# Crystal_Test_V1.net
KiCad netlist of a schematic drawn in Altium Designer
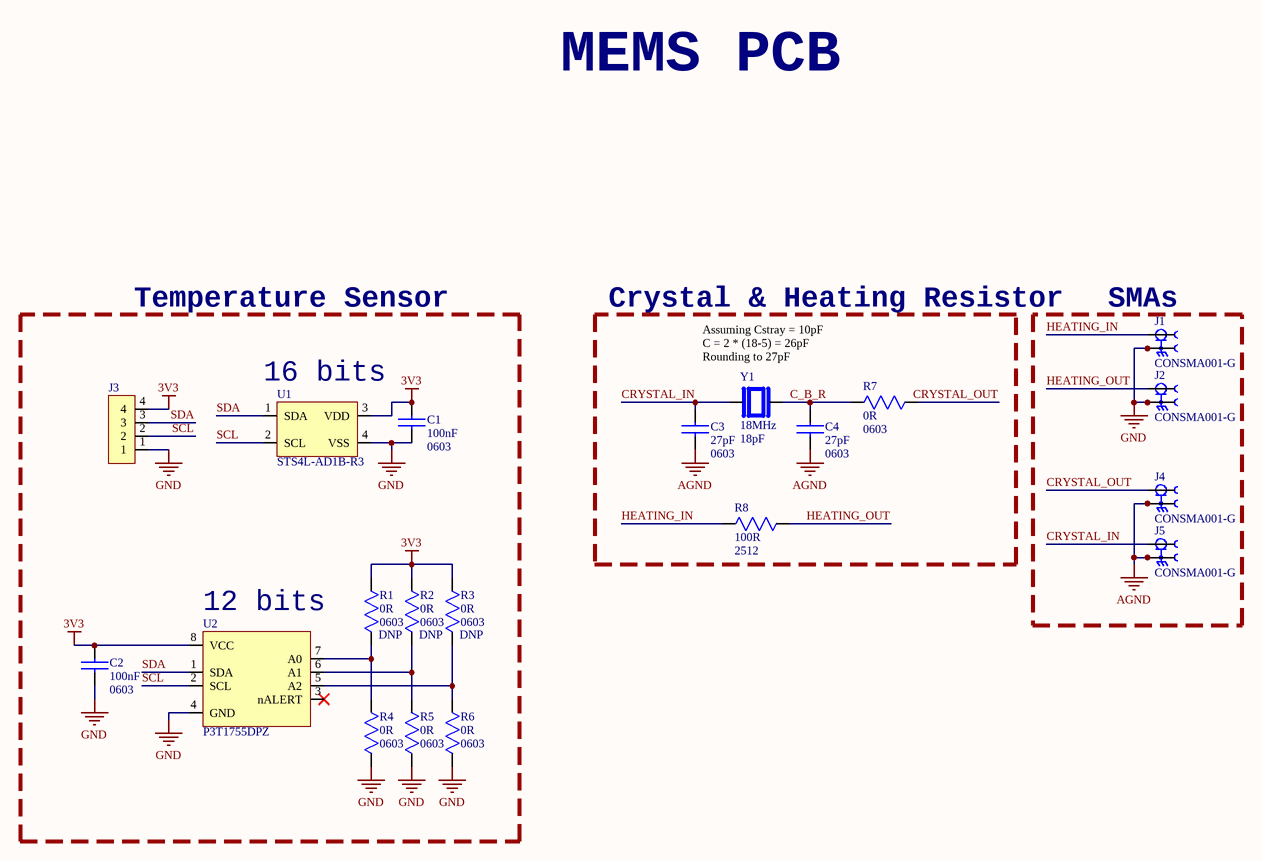
[diagram p0: Crystal_Test_V1.SchDoc]

(export (version "E")
  (design (tool "Eeschema 10.0.6"))
  (components
    (comp (ref "C1")
      (value "100nF")
      (footprint "C0603")
      (description "CAP CER 100NF 100V X8L 0603")
      (fields
        (field (name "MANUFACTURER") "Samsung")
        (field (name "MANUFACTURER PART NUMBER") "CL10E104KC8VPNC")
        (field (name "CASE") "0603")
      )
      (libsource (lib "MEMS_LIB") (part "CL10E104KC8VPNC"))
    )
    (comp (ref "C2")
      (value "100nF")
      (footprint "C0603")
      (description "CAP CER 100NF 100V X8L 0603")
      (fields
        (field (name "MANUFACTURER") "Samsung")
        (field (name "MANUFACTURER PART NUMBER") "CL10E104KC8VPNC")
        (field (name "CASE") "0603")
      )
      (libsource (lib "MEMS_LIB") (part "CL10E104KC8VPNC"))
    )
    (comp (ref "C3")
      (value "27pF")
      (footprint "C0603")
      (description "CAP CER 27PF 50V C0G/NP0 0603")
      (fields (field (name "PACKAGING") "0603") (field (name "Comment") "C0603C270J5GACTU"))
      (libsource (lib "MEMS_LIB") (part "C0603C270J5GACTU"))
    )
    (comp (ref "C4")
      (value "27pF")
      (footprint "C0603")
      (description "CAP CER 27PF 50V C0G/NP0 0603")
      (fields (field (name "PACKAGING") "0603") (field (name "Comment") "C0603C270J5GACTU"))
      (libsource (lib "MEMS_LIB") (part "C0603C270J5GACTU"))
    )
    (comp (ref "J1")
      (value "CONSMA001-G")
      (footprint "CONSMA001-G")
      (description "CONN SMA RCPT STR 50 OHM PCB")
      (libsource (lib "MEMS_LIB") (part "CONSMA001-G"))
    )
    (comp (ref "J2")
      (value "CONSMA001-G")
      (footprint "CONSMA001-G")
      (description "CONN SMA RCPT STR 50 OHM PCB")
      (libsource (lib "MEMS_LIB") (part "CONSMA001-G"))
    )
    (comp (ref "J3")
      (value "61300411121")
      (footprint "WURTH_61300411121")
      (description "CONN HEADER VERT 4POS 2.54MM")
      (fields (field (name "MF") "WÃ¼rth Elektronik"))
      (libsource (lib "MEMS_LIB") (part "61300411121"))
    )
    (comp (ref "J4")
      (value "CONSMA001-G")
      (footprint "CONSMA001-G")
      (description "CONN SMA RCPT STR 50 OHM PCB")
      (libsource (lib "MEMS_LIB") (part "CONSMA001-G"))
    )
    (comp (ref "J5")
      (value "CONSMA001-G")
      (footprint "CONSMA001-G")
      (description "CONN SMA RCPT STR 50 OHM PCB")
      (libsource (lib "MEMS_LIB") (part "CONSMA001-G"))
    )
    (comp (ref "R1")
      (value "0R")
      (footprint "R0603")
      (description "RES 0 OHM JUMPER 1/10W 0603")
      (fields
        (field (name "MF") "Stackpole Electronics")
        (field (name "MP") "RMCF0603ZT0R00")
        (field (name "PACKAGE") "0603")
      )
      (libsource (lib "MEMS_LIB") (part "RMCF0603ZT0R00"))
    )
    (comp (ref "R2")
      (value "0R")
      (footprint "R0603")
      (description "RES 0 OHM JUMPER 1/10W 0603")
      (fields
        (field (name "MF") "Stackpole Electronics")
        (field (name "MP") "RMCF0603ZT0R00")
        (field (name "PACKAGE") "0603")
      )
      (libsource (lib "MEMS_LIB") (part "RMCF0603ZT0R00"))
    )
    (comp (ref "R3")
      (value "0R")
      (footprint "R0603")
      (description "RES 0 OHM JUMPER 1/10W 0603")
      (fields
        (field (name "MF") "Stackpole Electronics")
        (field (name "MP") "RMCF0603ZT0R00")
        (field (name "PACKAGE") "0603")
      )
      (libsource (lib "MEMS_LIB") (part "RMCF0603ZT0R00"))
    )
    (comp (ref "R4")
      (value "0R")
      (footprint "R0603")
      (description "RES 0 OHM JUMPER 1/10W 0603")
      (fields
        (field (name "MF") "Stackpole Electronics")
        (field (name "MP") "RMCF0603ZT0R00")
        (field (name "PACKAGE") "0603")
      )
      (libsource (lib "MEMS_LIB") (part "RMCF0603ZT0R00"))
    )
    (comp (ref "R5")
      (value "0R")
      (footprint "R0603")
      (description "RES 0 OHM JUMPER 1/10W 0603")
      (fields
        (field (name "MF") "Stackpole Electronics")
        (field (name "MP") "RMCF0603ZT0R00")
        (field (name "PACKAGE") "0603")
      )
      (libsource (lib "MEMS_LIB") (part "RMCF0603ZT0R00"))
    )
    (comp (ref "R6")
      (value "0R")
      (footprint "R0603")
      (description "RES 0 OHM JUMPER 1/10W 0603")
      (fields
        (field (name "MF") "Stackpole Electronics")
        (field (name "MP") "RMCF0603ZT0R00")
        (field (name "PACKAGE") "0603")
      )
      (libsource (lib "MEMS_LIB") (part "RMCF0603ZT0R00"))
    )
    (comp (ref "R7")
      (value "0R")
      (footprint "R0603")
      (description "RES 0 OHM JUMPER 1/10W 0603")
      (fields
        (field (name "MF") "Stackpole Electronics")
        (field (name "MP") "RMCF0603ZT0R00")
        (field (name "PACKAGE") "0603")
      )
      (libsource (lib "MEMS_LIB") (part "RMCF0603ZT0R00"))
    )
    (comp (ref "R8")
      (value "100R")
      (footprint "R2512")
      (description "RES SMD 100 OHM 1% 1W 2512")
      (fields (field (name "PACKAGING") "2512") (field (name "Comment") "CRCW2512100RFKEG"))
      (libsource (lib "MEMS_LIB") (part "CRCW2512100RFKEG"))
    )
    (comp (ref "U1")
      (value "STS4L-AD1B-R3")
      (footprint "STS4L-AD1B-R3")
      (description "IC - TEMPERATURE SENSOR 4-DFN")
      (libsource (lib "MEMS_LIB") (part "STS4L-AD1B-R3"))
    )
    (comp (ref "U2")
      (value "P3T1755DPZ")
      (footprint "TSSOP8_P3T1755DPZ_NXP")
      (description "SENSOR DGTL -40C ~ 125C 8-TSSOP")
      (libsource (lib "MEMS_LIB") (part "P3T1755DPZ"))
    )
    (comp (ref "Y1")
      (value "18MHz")
      (footprint "XTAL_ABLS-18.000MHZ-B4-T")
      (description "CRYSTAL 18.0000MHZ 18PF SMD")
      (fields
        (field (name "MF") "Abracon")
        (field (name "MP") "ABLS-18.000MHZ-B4-T")
        (field (name "CAPACITANCE") "18pF")
      )
      (libsource (lib "MEMS_LIB") (part "ABLS-18.000MHZ-B4-T"))
    )
  )
  (nets
    (net (code "1") (name "/CRYSTAL_IN") (class "Default")
      (node (ref "C3") (pin "1") (pinfunction "1_1") (pintype "passive"))
      (node (ref "J5") (pin "1") (pinfunction "1_1") (pintype "passive"))
      (node (ref "Y1") (pin "1") (pinfunction "1_1") (pintype "passive"))
    )
    (net (code "2") (name "/CRYSTAL_OUT") (class "Default")
      (node (ref "J4") (pin "1") (pinfunction "1_1") (pintype "passive"))
      (node (ref "R7") (pin "1") (pinfunction "1_1") (pintype "passive"))
    )
    (net (code "3") (name "/C_B_R") (class "Default")
      (node (ref "C4") (pin "1") (pinfunction "1_1") (pintype "passive"))
      (node (ref "R7") (pin "2") (pinfunction "2_2") (pintype "passive"))
      (node (ref "Y1") (pin "2") (pinfunction "2_2") (pintype "passive"))
    )
    (net (code "4") (name "/HEATING_IN") (class "Default")
      (node (ref "J1") (pin "1") (pinfunction "1_1") (pintype "passive"))
      (node (ref "R8") (pin "1") (pinfunction "1_1") (pintype "passive"))
    )
    (net (code "5") (name "/HEATING_OUT") (class "Default")
      (node (ref "J2") (pin "1") (pinfunction "1_1") (pintype "passive"))
      (node (ref "R8") (pin "2") (pinfunction "2_2") (pintype "passive"))
    )
    (net (code "6") (name "/SCL") (class "Default")
      (node (ref "J3") (pin "2") (pinfunction "2_2") (pintype "passive"))
      (node (ref "U1") (pin "2") (pinfunction "SCL_2") (pintype "passive"))
      (node (ref "U2") (pin "2") (pinfunction "SCL_2") (pintype "passive"))
    )
    (net (code "7") (name "/SDA") (class "Default")
      (node (ref "J3") (pin "3") (pinfunction "3_3") (pintype "passive"))
      (node (ref "U1") (pin "1") (pinfunction "SDA_1") (pintype "passive"))
      (node (ref "U2") (pin "1") (pinfunction "SDA_1") (pintype "passive"))
    )
    (net (code "8") (name "3V3") (class "Default")
      (node (ref "C1") (pin "1") (pinfunction "1_1") (pintype "passive"))
      (node (ref "C2") (pin "1") (pinfunction "1_1") (pintype "passive"))
      (node (ref "J3") (pin "4") (pinfunction "4_4") (pintype "passive"))
      (node (ref "R1") (pin "2") (pinfunction "2_2") (pintype "passive"))
      (node (ref "R2") (pin "2") (pinfunction "2_2") (pintype "passive"))
      (node (ref "R3") (pin "2") (pinfunction "2_2") (pintype "passive"))
      (node (ref "U1") (pin "3") (pinfunction "VDD_3") (pintype "passive"))
      (node (ref "U2") (pin "8") (pinfunction "VCC_8") (pintype "power_in"))
    )
    (net (code "9") (name "AGND") (class "Default")
      (node (ref "C3") (pin "2") (pinfunction "2_2") (pintype "passive"))
      (node (ref "C4") (pin "2") (pinfunction "2_2") (pintype "passive"))
      (node (ref "J4") (pin "S1") (pinfunction "2_S1") (pintype "passive"))
      (node (ref "J4") (pin "S2") (pinfunction "2_S2") (pintype "passive"))
      (node (ref "J4") (pin "S3") (pinfunction "2_S3") (pintype "passive"))
      (node (ref "J4") (pin "S4") (pinfunction "2_S4") (pintype "passive"))
      (node (ref "J5") (pin "S1") (pinfunction "2_S1") (pintype "passive"))
      (node (ref "J5") (pin "S2") (pinfunction "2_S2") (pintype "passive"))
      (node (ref "J5") (pin "S3") (pinfunction "2_S3") (pintype "passive"))
      (node (ref "J5") (pin "S4") (pinfunction "2_S4") (pintype "passive"))
    )
    (net (code "10") (name "GND") (class "Default")
      (node (ref "C1") (pin "2") (pinfunction "2_2") (pintype "passive"))
      (node (ref "C2") (pin "2") (pinfunction "2_2") (pintype "passive"))
      (node (ref "J1") (pin "S1") (pinfunction "2_S1") (pintype "passive"))
      (node (ref "J1") (pin "S2") (pinfunction "2_S2") (pintype "passive"))
      (node (ref "J1") (pin "S3") (pinfunction "2_S3") (pintype "passive"))
      (node (ref "J1") (pin "S4") (pinfunction "2_S4") (pintype "passive"))
      (node (ref "J2") (pin "S1") (pinfunction "2_S1") (pintype "passive"))
      (node (ref "J2") (pin "S2") (pinfunction "2_S2") (pintype "passive"))
      (node (ref "J2") (pin "S3") (pinfunction "2_S3") (pintype "passive"))
      (node (ref "J2") (pin "S4") (pinfunction "2_S4") (pintype "passive"))
      (node (ref "J3") (pin "1") (pinfunction "1_1") (pintype "passive"))
      (node (ref "R4") (pin "1") (pinfunction "1_1") (pintype "passive"))
      (node (ref "R5") (pin "1") (pinfunction "1_1") (pintype "passive"))
      (node (ref "R6") (pin "1") (pinfunction "1_1") (pintype "passive"))
      (node (ref "U1") (pin "4") (pinfunction "VSS_4") (pintype "passive"))
      (node (ref "U2") (pin "4") (pinfunction "GND_4") (pintype "power_in"))
    )
    (net (code "11") (name "Net-(U2-A0)") (class "Default")
      (node (ref "R1") (pin "1") (pinfunction "1_1") (pintype "passive"))
      (node (ref "R4") (pin "2") (pinfunction "2_2") (pintype "passive"))
      (node (ref "U2") (pin "7") (pinfunction "A0_7") (pintype "passive"))
    )
    (net (code "12") (name "Net-(U2-A1)") (class "Default")
      (node (ref "R2") (pin "1") (pinfunction "1_1") (pintype "passive"))
      (node (ref "R5") (pin "2") (pinfunction "2_2") (pintype "passive"))
      (node (ref "U2") (pin "6") (pinfunction "A1_6") (pintype "passive"))
    )
    (net (code "13") (name "Net-(U2-A2)") (class "Default")
      (node (ref "R3") (pin "1") (pinfunction "1_1") (pintype "passive"))
      (node (ref "R6") (pin "2") (pinfunction "2_2") (pintype "passive"))
      (node (ref "U2") (pin "5") (pinfunction "A2_5") (pintype "passive"))
    )
    (net (code "14") (name "unconnected-(U2-nALERT-Pad3)") (class "Default")
      (node (ref "U2") (pin "3") (pinfunction "nALERT_3") (pintype "passive+no_connect"))
    )
  )
)
